# holmes_ups.net
KiCad netlist of a schematic drawn in EAGLE
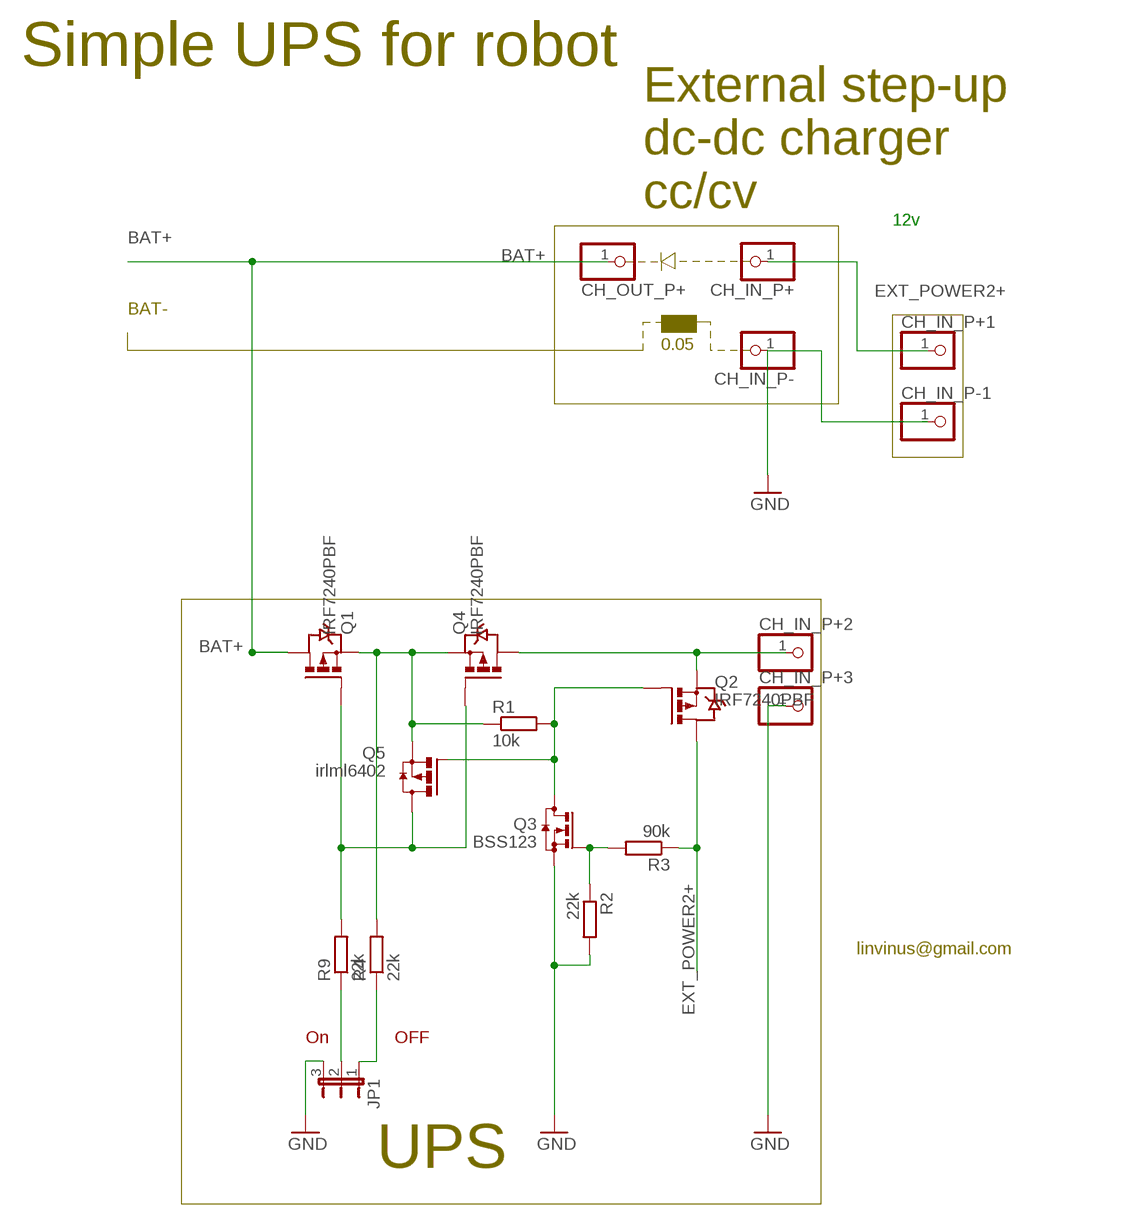
[diagram p0: schematic, sheet 1]

(export (version "E")
  (design (tool "Eeschema 10.0.6"))
  (components
    (comp (ref "CH_IN_P+")
      (value "PINHD-1X1")
      (footprint "eagle-import:1X01")
      (libsource (lib "eagle-import") (part "PINHD-1X1"))
    )
    (comp (ref "CH_IN_P+1")
      (value "PINHD-1X1")
      (footprint "eagle-import:1X01")
      (libsource (lib "eagle-import") (part "PINHD-1X1"))
    )
    (comp (ref "CH_IN_P+2")
      (value "PINHD-1X1")
      (footprint "eagle-import:1X01")
      (libsource (lib "eagle-import") (part "PINHD-1X1"))
    )
    (comp (ref "CH_IN_P+3")
      (value "PINHD-1X1")
      (footprint "eagle-import:1X01")
      (libsource (lib "eagle-import") (part "PINHD-1X1"))
    )
    (comp (ref "CH_IN_P-")
      (value "PINHD-1X1")
      (footprint "eagle-import:1X01")
      (libsource (lib "eagle-import") (part "PINHD-1X1"))
    )
    (comp (ref "CH_IN_P-1")
      (value "PINHD-1X1")
      (footprint "eagle-import:1X01")
      (libsource (lib "eagle-import") (part "PINHD-1X1"))
    )
    (comp (ref "CH_OUT_P+")
      (value "PINHD-1X1")
      (footprint "eagle-import:1X01")
      (libsource (lib "eagle-import") (part "PINHD-1X1"))
    )
    (comp (ref "JP1")
      (value "JP2E")
      (footprint "eagle-import:JP2")
      (libsource (lib "eagle-import") (part "JP2E"))
    )
    (comp (ref "Q1")
      (value "IRF7240PBF")
      (footprint "eagle-import:SO-08")
      (libsource (lib "eagle-import") (part "P-MOSFET-SO8"))
    )
    (comp (ref "Q2")
      (value "IRF7240PBF")
      (footprint "eagle-import:SO-08")
      (libsource (lib "eagle-import") (part "P-MOSFET-SO8"))
    )
    (comp (ref "Q3")
      (value "BSS123")
      (footprint "eagle-import:SOT23")
      (libsource (lib "eagle-import") (part "BSS123"))
    )
    (comp (ref "Q4")
      (value "IRF7240PBF")
      (footprint "eagle-import:SO-08")
      (libsource (lib "eagle-import") (part "P-MOSFET-SO8"))
    )
    (comp (ref "Q5")
      (value "irlml6402")
      (footprint "eagle-import:SUPER-SOT3")
      (libsource (lib "eagle-import") (part "FDN360P"))
    )
    (comp (ref "R1")
      (value "10k")
      (footprint "eagle-import:R0805")
      (libsource (lib "eagle-import") (part "R-EU_R0805"))
    )
    (comp (ref "R2")
      (value "22k")
      (footprint "eagle-import:R0805")
      (libsource (lib "eagle-import") (part "R-EU_R0805"))
    )
    (comp (ref "R3")
      (value "90k")
      (footprint "eagle-import:R0805")
      (libsource (lib "eagle-import") (part "R-EU_R0805"))
    )
    (comp (ref "R4")
      (value "22k")
      (footprint "eagle-import:R0805")
      (libsource (lib "eagle-import") (part "R-EU_R0805"))
    )
    (comp (ref "R9")
      (value "22k")
      (footprint "eagle-import:R0805")
      (libsource (lib "eagle-import") (part "R-EU_R0805"))
    )
  )
  (nets
    (net (code "1") (name "/BAT+") (class "Default")
      (node (ref "CH_OUT_P+") (pin "1") (pinfunction "1_1") (pintype "passive"))
      (node (ref "Q1") (pin "5") (pinfunction "D_5") (pintype "passive"))
      (node (ref "Q1") (pin "6") (pinfunction "D_6") (pintype "passive"))
      (node (ref "Q1") (pin "7") (pinfunction "D_7") (pintype "passive"))
      (node (ref "Q1") (pin "8") (pinfunction "D_8") (pintype "passive"))
    )
    (net (code "2") (name "/EXT_POWER2+") (class "Default")
      (node (ref "CH_IN_P+") (pin "1") (pinfunction "1_1") (pintype "passive"))
      (node (ref "CH_IN_P+1") (pin "1") (pinfunction "1_1") (pintype "passive"))
      (node (ref "Q2") (pin "5") (pinfunction "D_5") (pintype "passive"))
      (node (ref "Q2") (pin "6") (pinfunction "D_6") (pintype "passive"))
      (node (ref "Q2") (pin "7") (pinfunction "D_7") (pintype "passive"))
      (node (ref "Q2") (pin "8") (pinfunction "D_8") (pintype "passive"))
      (node (ref "R3") (pin "1") (pinfunction "1_1") (pintype "passive"))
    )
    (net (code "3") (name "GND") (class "Default")
      (node (ref "CH_IN_P+3") (pin "1") (pinfunction "1_1") (pintype "passive"))
      (node (ref "CH_IN_P-") (pin "1") (pinfunction "1_1") (pintype "passive"))
      (node (ref "CH_IN_P-1") (pin "1") (pinfunction "1_1") (pintype "passive"))
      (node (ref "JP1") (pin "3") (pinfunction "3_3") (pintype "passive"))
      (node (ref "Q3") (pin "2") (pinfunction "S_2") (pintype "passive"))
      (node (ref "R2") (pin "2") (pinfunction "2_2") (pintype "passive"))
    )
    (net (code "4") (name "Net-(CH_IN_P+2-Pad1)") (class "Default")
      (node (ref "CH_IN_P+2") (pin "1") (pinfunction "1_1") (pintype "passive"))
      (node (ref "Q2") (pin "1") (pinfunction "S_1") (pintype "passive"))
      (node (ref "Q2") (pin "2") (pinfunction "S_2") (pintype "passive"))
      (node (ref "Q2") (pin "3") (pinfunction "S_3") (pintype "passive"))
      (node (ref "Q4") (pin "5") (pinfunction "D_5") (pintype "passive"))
      (node (ref "Q4") (pin "6") (pinfunction "D_6") (pintype "passive"))
      (node (ref "Q4") (pin "7") (pinfunction "D_7") (pintype "passive"))
      (node (ref "Q4") (pin "8") (pinfunction "D_8") (pintype "passive"))
    )
    (net (code "5") (name "Net-(JP1-Pad1)") (class "Default")
      (node (ref "JP1") (pin "1") (pinfunction "1_1") (pintype "passive"))
      (node (ref "R4") (pin "1") (pinfunction "1_1") (pintype "passive"))
    )
    (net (code "6") (name "Net-(JP1-Pad2)") (class "Default")
      (node (ref "JP1") (pin "2") (pinfunction "2_2") (pintype "passive"))
      (node (ref "R9") (pin "1") (pinfunction "1_1") (pintype "passive"))
    )
    (net (code "7") (name "Net-(Q1-G)") (class "Default")
      (node (ref "Q1") (pin "4") (pinfunction "G_4") (pintype "passive"))
      (node (ref "Q4") (pin "4") (pinfunction "G_4") (pintype "passive"))
      (node (ref "Q5") (pin "3") (pinfunction "D_3") (pintype "passive"))
      (node (ref "R9") (pin "2") (pinfunction "2_2") (pintype "passive"))
    )
    (net (code "8") (name "Net-(Q2-G)") (class "Default")
      (node (ref "Q2") (pin "4") (pinfunction "G_4") (pintype "passive"))
      (node (ref "Q3") (pin "3") (pinfunction "D_3") (pintype "passive"))
      (node (ref "Q5") (pin "1") (pinfunction "G_1") (pintype "passive"))
      (node (ref "R1") (pin "2") (pinfunction "2_2") (pintype "passive"))
    )
    (net (code "9") (name "Net-(Q3-G)") (class "Default")
      (node (ref "Q3") (pin "1") (pinfunction "G_1") (pintype "passive"))
      (node (ref "R2") (pin "1") (pinfunction "1_1") (pintype "passive"))
      (node (ref "R3") (pin "2") (pinfunction "2_2") (pintype "passive"))
    )
    (net (code "10") (name "Net-(Q5-S)") (class "Default")
      (node (ref "Q1") (pin "1") (pinfunction "S_1") (pintype "passive"))
      (node (ref "Q1") (pin "2") (pinfunction "S_2") (pintype "passive"))
      (node (ref "Q1") (pin "3") (pinfunction "S_3") (pintype "passive"))
      (node (ref "Q4") (pin "1") (pinfunction "S_1") (pintype "passive"))
      (node (ref "Q4") (pin "2") (pinfunction "S_2") (pintype "passive"))
      (node (ref "Q4") (pin "3") (pinfunction "S_3") (pintype "passive"))
      (node (ref "Q5") (pin "2") (pinfunction "S_2") (pintype "passive"))
      (node (ref "R1") (pin "1") (pinfunction "1_1") (pintype "passive"))
      (node (ref "R4") (pin "2") (pinfunction "2_2") (pintype "passive"))
    )
  )
)
